# Schematic.net
KiCad netlist of a schematic drawn in Altium Designer
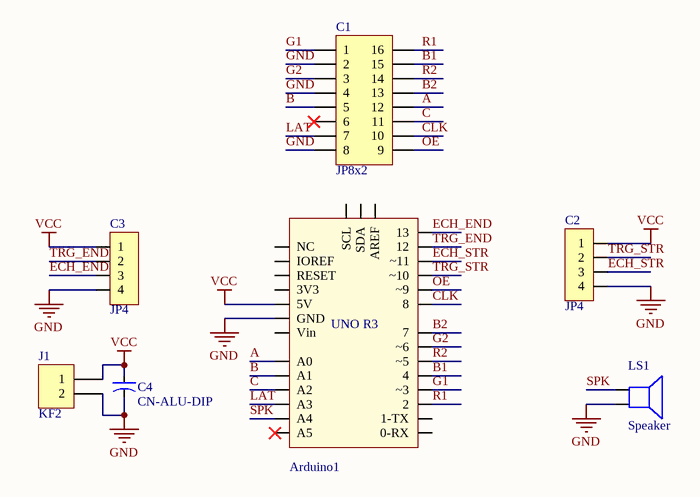
[diagram p0: Schematic.SchDoc]

(export (version "E")
  (design (tool "Eeschema 10.0.6"))
  (components
    (comp (ref "Arduino1")
      (value "Arduino Uno R3")
      (footprint "Arduino UNO R3")
      (description "Arduino UNO R3")
      (libsource (lib "LIBRARY") (part "Arduino Uno R3"))
    )
    (comp (ref "C1")
      (value "JP8x2")
      (footprint "JP8-C2T")
      (description "WR-PHD 2.54 mm Dual Socket Header")
      (fields
        (field (name "MANUFACTURER") "Würth Elektronik eiSos GmbH")
        (field (name "PARTNO") "61301621821")
        (field (name "CREATED BY") "Karrer Zheng")
      )
      (libsource (lib "LIBRARY") (part "JP8x2"))
    )
    (comp (ref "C2")
      (value "JP4")
      (footprint "JP4-C1T")
      (description "WR-PHD 2.54 mm Angled Socket Header")
      (fields
        (field (name "MANUFACTURER") "Würth Elektronik eiSos GmbH")
        (field (name "PARTNO") "613004143121")
        (field (name "CREATED BY") "Karrer Zheng")
      )
      (libsource (lib "") (part "JP4_1"))
    )
    (comp (ref "C3")
      (value "JP4")
      (footprint "JP4-C1T")
      (description "WR-PHD 2.54 mm Angled Socket Header")
      (fields
        (field (name "MANUFACTURER") "Würth Elektronik eiSos GmbH")
        (field (name "PARTNO") "613004143121")
        (field (name "CREATED BY") "Karrer Zheng")
      )
      (libsource (lib "LIBRARY") (part "JP4"))
    )
    (comp (ref "C4")
      (value "CN-ALU-DIP")
      (footprint "CA-ALU-2.54")
      (description "Capacitor (Semiconductor SIM Model)")
      (fields (field (name "PUBLISHER") "Altium Limited"))
      (libsource (lib "LIBRARY") (part "CN-ALU-DIP"))
    )
    (comp (ref "J1")
      (value "KF2")
      (footprint "KF2-3.5")
      (fields
        (field (name "MANUFACTURER") "Würth Elektronik eiSos GmbH")
        (field (name "PARTNO") "691103110002")
        (field (name "CREATED BY") "Karrer Zheng")
      )
      (libsource (lib "LIBRARY") (part "KF2"))
    )
    (comp (ref "LS1")
      (value "Speaker")
      (footprint "SPEAKER")
      (description "Loudspeaker")
      (fields (field (name "PUBLISHER") "Altium Limited"))
      (libsource (lib "LIBRARY") (part "Speaker"))
    )
  )
  (nets
    (net (code "1") (name "/A") (class "Default")
      (node (ref "Arduino1") (pin "A0") (pinfunction "A0_A0") (pintype "passive"))
      (node (ref "C1") (pin "12") (pinfunction "12_12") (pintype "passive"))
    )
    (net (code "2") (name "/B") (class "Default")
      (node (ref "Arduino1") (pin "A1") (pinfunction "A1_A1") (pintype "passive"))
      (node (ref "C1") (pin "5") (pinfunction "5_5") (pintype "passive"))
    )
    (net (code "3") (name "/B1") (class "Default")
      (node (ref "Arduino1") (pin "4") (pinfunction "4_4") (pintype "passive"))
      (node (ref "C1") (pin "15") (pinfunction "15_15") (pintype "passive"))
    )
    (net (code "4") (name "/B2") (class "Default")
      (node (ref "Arduino1") (pin "7") (pinfunction "7_7") (pintype "passive"))
      (node (ref "C1") (pin "13") (pinfunction "13_13") (pintype "passive"))
    )
    (net (code "5") (name "/C") (class "Default")
      (node (ref "Arduino1") (pin "A2") (pinfunction "A2_A2") (pintype "passive"))
      (node (ref "C1") (pin "11") (pinfunction "11_11") (pintype "passive"))
    )
    (net (code "6") (name "/CLK") (class "Default")
      (node (ref "Arduino1") (pin "8") (pinfunction "8_8") (pintype "passive"))
      (node (ref "C1") (pin "10") (pinfunction "10_10") (pintype "passive"))
    )
    (net (code "7") (name "/ECH_END") (class "Default")
      (node (ref "Arduino1") (pin "13") (pinfunction "13_13") (pintype "passive"))
      (node (ref "C3") (pin "3") (pinfunction "3_3") (pintype "passive"))
    )
    (net (code "8") (name "/ECH_STR") (class "Default")
      (node (ref "Arduino1") (pin "~11") (pinfunction "~11_~11") (pintype "passive"))
      (node (ref "C2") (pin "3") (pinfunction "3_3") (pintype "passive"))
    )
    (net (code "9") (name "/G1") (class "Default")
      (node (ref "Arduino1") (pin "~3") (pinfunction "~3_~3") (pintype "passive"))
      (node (ref "C1") (pin "1") (pinfunction "1_1") (pintype "passive"))
    )
    (net (code "10") (name "/G2") (class "Default")
      (node (ref "Arduino1") (pin "~6") (pinfunction "~6_~6") (pintype "passive"))
      (node (ref "C1") (pin "3") (pinfunction "3_3") (pintype "passive"))
    )
    (net (code "11") (name "/LAT") (class "Default")
      (node (ref "Arduino1") (pin "A3") (pinfunction "A3_A3") (pintype "passive"))
      (node (ref "C1") (pin "7") (pinfunction "7_7") (pintype "passive"))
    )
    (net (code "12") (name "/OE") (class "Default")
      (node (ref "Arduino1") (pin "~9") (pinfunction "~9_~9") (pintype "passive"))
      (node (ref "C1") (pin "9") (pinfunction "9_9") (pintype "passive"))
    )
    (net (code "13") (name "/R1") (class "Default")
      (node (ref "Arduino1") (pin "2") (pinfunction "2_2") (pintype "passive"))
      (node (ref "C1") (pin "16") (pinfunction "16_16") (pintype "passive"))
    )
    (net (code "14") (name "/R2") (class "Default")
      (node (ref "Arduino1") (pin "~5") (pinfunction "~5_~5") (pintype "passive"))
      (node (ref "C1") (pin "14") (pinfunction "14_14") (pintype "passive"))
    )
    (net (code "15") (name "/SPK") (class "Default")
      (node (ref "Arduino1") (pin "A4") (pinfunction "A4_A4") (pintype "passive"))
      (node (ref "LS1") (pin "1") (pinfunction "1_1") (pintype "passive"))
    )
    (net (code "16") (name "/TRG_END") (class "Default")
      (node (ref "Arduino1") (pin "12") (pinfunction "12_12") (pintype "passive"))
      (node (ref "C3") (pin "2") (pinfunction "2_2") (pintype "passive"))
    )
    (net (code "17") (name "/TRG_STR") (class "Default")
      (node (ref "Arduino1") (pin "~10") (pinfunction "~10_~10") (pintype "passive"))
      (node (ref "C2") (pin "2") (pinfunction "2_2") (pintype "passive"))
    )
    (net (code "18") (name "GND") (class "Default")
      (node (ref "Arduino1") (pin "GND") (pinfunction "GND_GND") (pintype "passive"))
      (node (ref "C1") (pin "2") (pinfunction "2_2") (pintype "passive"))
      (node (ref "C1") (pin "4") (pinfunction "4_4") (pintype "passive"))
      (node (ref "C1") (pin "8") (pinfunction "8_8") (pintype "passive"))
      (node (ref "C2") (pin "4") (pinfunction "4_4") (pintype "passive"))
      (node (ref "C3") (pin "4") (pinfunction "4_4") (pintype "passive"))
      (node (ref "C4") (pin "2") (pinfunction "2_2") (pintype "passive"))
      (node (ref "J1") (pin "2") (pinfunction "2_2") (pintype "passive"))
      (node (ref "LS1") (pin "2") (pinfunction "2_2") (pintype "passive"))
    )
    (net (code "19") (name "VCC") (class "Default")
      (node (ref "Arduino1") (pin "5V") (pinfunction "5V_5V") (pintype "passive"))
      (node (ref "C2") (pin "1") (pinfunction "1_1") (pintype "passive"))
      (node (ref "C3") (pin "1") (pinfunction "1_1") (pintype "passive"))
      (node (ref "C4") (pin "1") (pinfunction "1_1") (pintype "passive"))
      (node (ref "J1") (pin "1") (pinfunction "1_1") (pintype "passive"))
    )
    (net (code "20") (name "unconnected-(Arduino1-Pad0-RX)") (class "Default")
      (node (ref "Arduino1") (pin "0-RX") (pinfunction "0-RX_0-RX") (pintype "passive"))
    )
    (net (code "21") (name "unconnected-(Arduino1-Pad1-TX)") (class "Default")
      (node (ref "Arduino1") (pin "1-TX") (pinfunction "1-TX_1-TX") (pintype "passive"))
    )
    (net (code "22") (name "unconnected-(Arduino1-Pad3V3)") (class "Default")
      (node (ref "Arduino1") (pin "3V3") (pinfunction "3V3_3V3") (pintype "passive"))
    )
    (net (code "23") (name "unconnected-(Arduino1-PadA5)") (class "Default")
      (node (ref "Arduino1") (pin "A5") (pinfunction "A5_A5") (pintype "passive+no_connect"))
    )
    (net (code "24") (name "unconnected-(Arduino1-PadAREF)") (class "Default")
      (node (ref "Arduino1") (pin "AREF") (pinfunction "AREF_AREF") (pintype "passive"))
    )
    (net (code "25") (name "unconnected-(Arduino1-PadIOREF)") (class "Default")
      (node (ref "Arduino1") (pin "IOREF") (pinfunction "IOREF_IOREF") (pintype "passive"))
    )
    (net (code "26") (name "unconnected-(Arduino1-PadNC)") (class "Default")
      (node (ref "Arduino1") (pin "NC") (pinfunction "NC_NC") (pintype "passive"))
    )
    (net (code "27") (name "unconnected-(Arduino1-PadRESET)") (class "Default")
      (node (ref "Arduino1") (pin "RESET") (pinfunction "RESET_RESET") (pintype "passive"))
    )
    (net (code "28") (name "unconnected-(Arduino1-PadSCL)") (class "Default")
      (node (ref "Arduino1") (pin "SCL") (pinfunction "SCL_SCL") (pintype "passive"))
    )
    (net (code "29") (name "unconnected-(Arduino1-PadSDA)") (class "Default")
      (node (ref "Arduino1") (pin "SDA") (pinfunction "SDA_SDA") (pintype "passive"))
    )
    (net (code "30") (name "unconnected-(Arduino1-PadVin)") (class "Default")
      (node (ref "Arduino1") (pin "Vin") (pinfunction "Vin_Vin") (pintype "passive"))
    )
    (net (code "31") (name "unconnected-(C1-Pad6)") (class "Default")
      (node (ref "C1") (pin "6") (pinfunction "6_6") (pintype "passive+no_connect"))
    )
  )
)
